# SDRPager_Interface.net
KiCad netlist of a schematic drawn in EAGLE
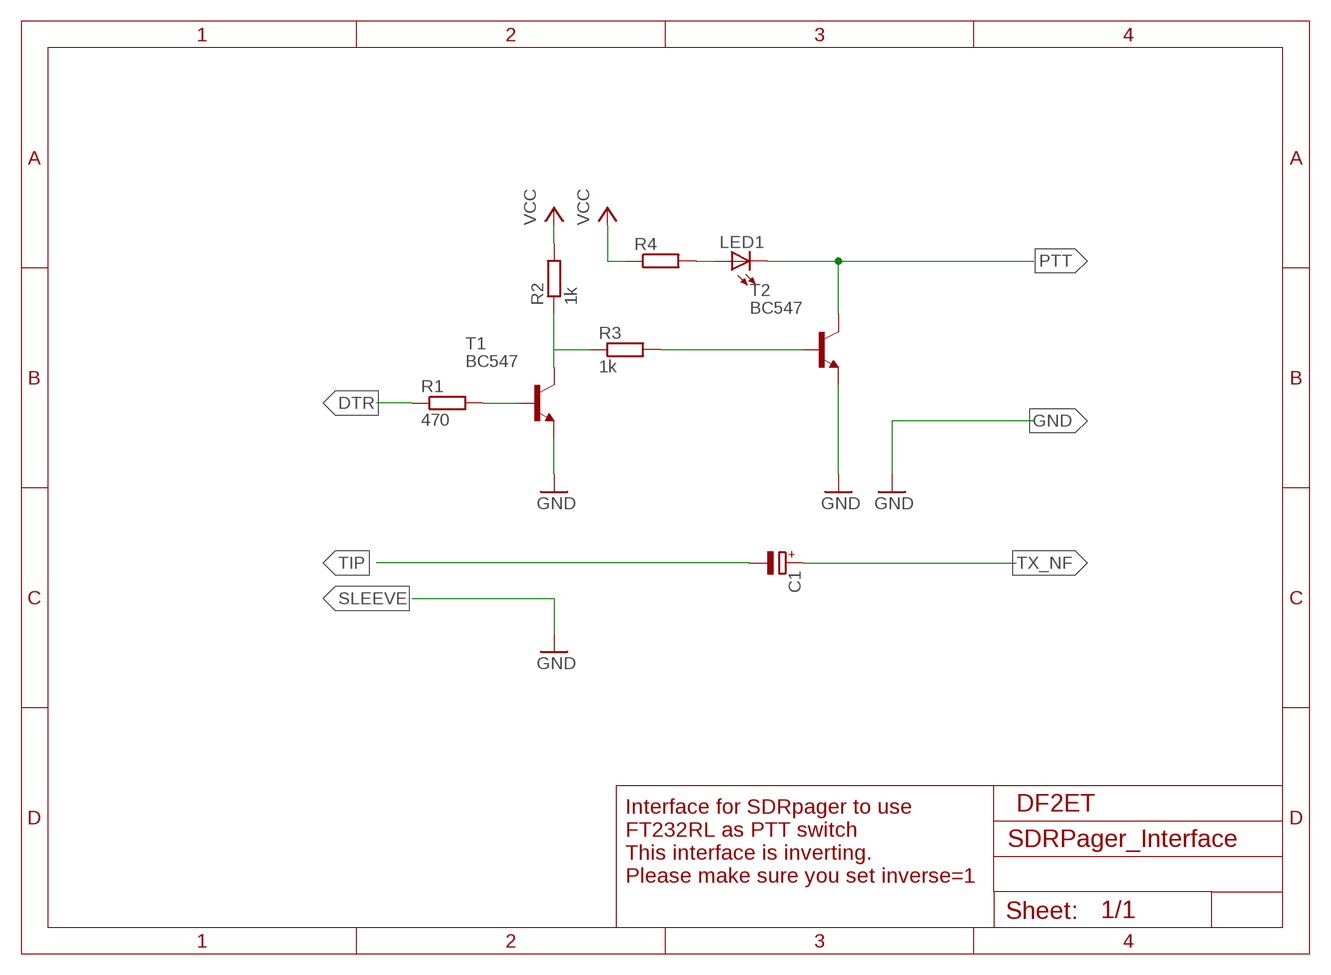
[diagram p0: schematic, sheet 1]

(export (version "E")
  (design (tool "Eeschema 10.0.6"))
  (components
    (comp (ref "C1")
      (value "CPOL-EUE2,5-6E")
      (footprint "eagle-import:E2,5-6E")
      (libsource (lib "eagle-import") (part "CPOL-EUE2,5-6E"))
    )
    (comp (ref "LED1")
      (value "LED3MM")
      (footprint "eagle-import:LED3MM")
      (libsource (lib "eagle-import") (part "LED3MM"))
    )
    (comp (ref "R1")
      (value "470")
      (footprint "eagle-import:0204_7")
      (libsource (lib "eagle-import") (part "R-EU_0204/7"))
    )
    (comp (ref "R2")
      (value "1k")
      (footprint "eagle-import:0204_7")
      (libsource (lib "eagle-import") (part "R-EU_0204/7"))
    )
    (comp (ref "R3")
      (value "1k")
      (footprint "eagle-import:0204_7")
      (libsource (lib "eagle-import") (part "R-EU_0204/7"))
    )
    (comp (ref "R4")
      (value "R-EU_0204/7")
      (footprint "eagle-import:0204_7")
      (libsource (lib "eagle-import") (part "R-EU_0204/7"))
    )
    (comp (ref "T1")
      (value "BC547")
      (footprint "eagle-import:TO92")
      (libsource (lib "eagle-import") (part "BC547"))
    )
    (comp (ref "T2")
      (value "BC547")
      (footprint "eagle-import:TO92")
      (libsource (lib "eagle-import") (part "BC547"))
    )
  )
  (nets
    (net (code "1") (name "DTR") (class "Default")
      (node (ref "R1") (pin "1") (pinfunction "1_1") (pintype "passive"))
    )
    (net (code "2") (name "GND") (class "Default")
      (node (ref "T1") (pin "1") (pinfunction "E_1") (pintype "passive"))
      (node (ref "T2") (pin "1") (pinfunction "E_1") (pintype "passive"))
    )
    (net (code "3") (name "Net-(LED1-PadA)") (class "Default")
      (node (ref "LED1") (pin "A") (pinfunction "A_A") (pintype "passive"))
      (node (ref "R4") (pin "2") (pinfunction "2_2") (pintype "passive"))
    )
    (net (code "4") (name "Net-(T1-B)") (class "Default")
      (node (ref "R1") (pin "2") (pinfunction "2_2") (pintype "passive"))
      (node (ref "T1") (pin "2") (pinfunction "B_2") (pintype "passive"))
    )
    (net (code "5") (name "Net-(T1-C)") (class "Default")
      (node (ref "R2") (pin "1") (pinfunction "1_1") (pintype "passive"))
      (node (ref "R3") (pin "1") (pinfunction "1_1") (pintype "passive"))
      (node (ref "T1") (pin "3") (pinfunction "C_3") (pintype "passive"))
    )
    (net (code "6") (name "Net-(T2-B)") (class "Default")
      (node (ref "R3") (pin "2") (pinfunction "2_2") (pintype "passive"))
      (node (ref "T2") (pin "2") (pinfunction "B_2") (pintype "passive"))
    )
    (net (code "7") (name "PTT") (class "Default")
      (node (ref "LED1") (pin "K") (pinfunction "C_K") (pintype "passive"))
      (node (ref "T2") (pin "3") (pinfunction "C_3") (pintype "passive"))
    )
    (net (code "8") (name "TIP") (class "Default")
      (node (ref "C1") (pin "-") (pinfunction "-_-") (pintype "passive"))
    )
    (net (code "9") (name "TX_NF") (class "Default")
      (node (ref "C1") (pin "+") (pinfunction "+_+") (pintype "passive"))
    )
    (net (code "10") (name "VCC") (class "Default")
      (node (ref "R2") (pin "2") (pinfunction "2_2") (pintype "passive"))
      (node (ref "R4") (pin "1") (pinfunction "1_1") (pintype "passive"))
    )
  )
)
